# displayBoard.net
KiCad netlist of a schematic drawn in EAGLE
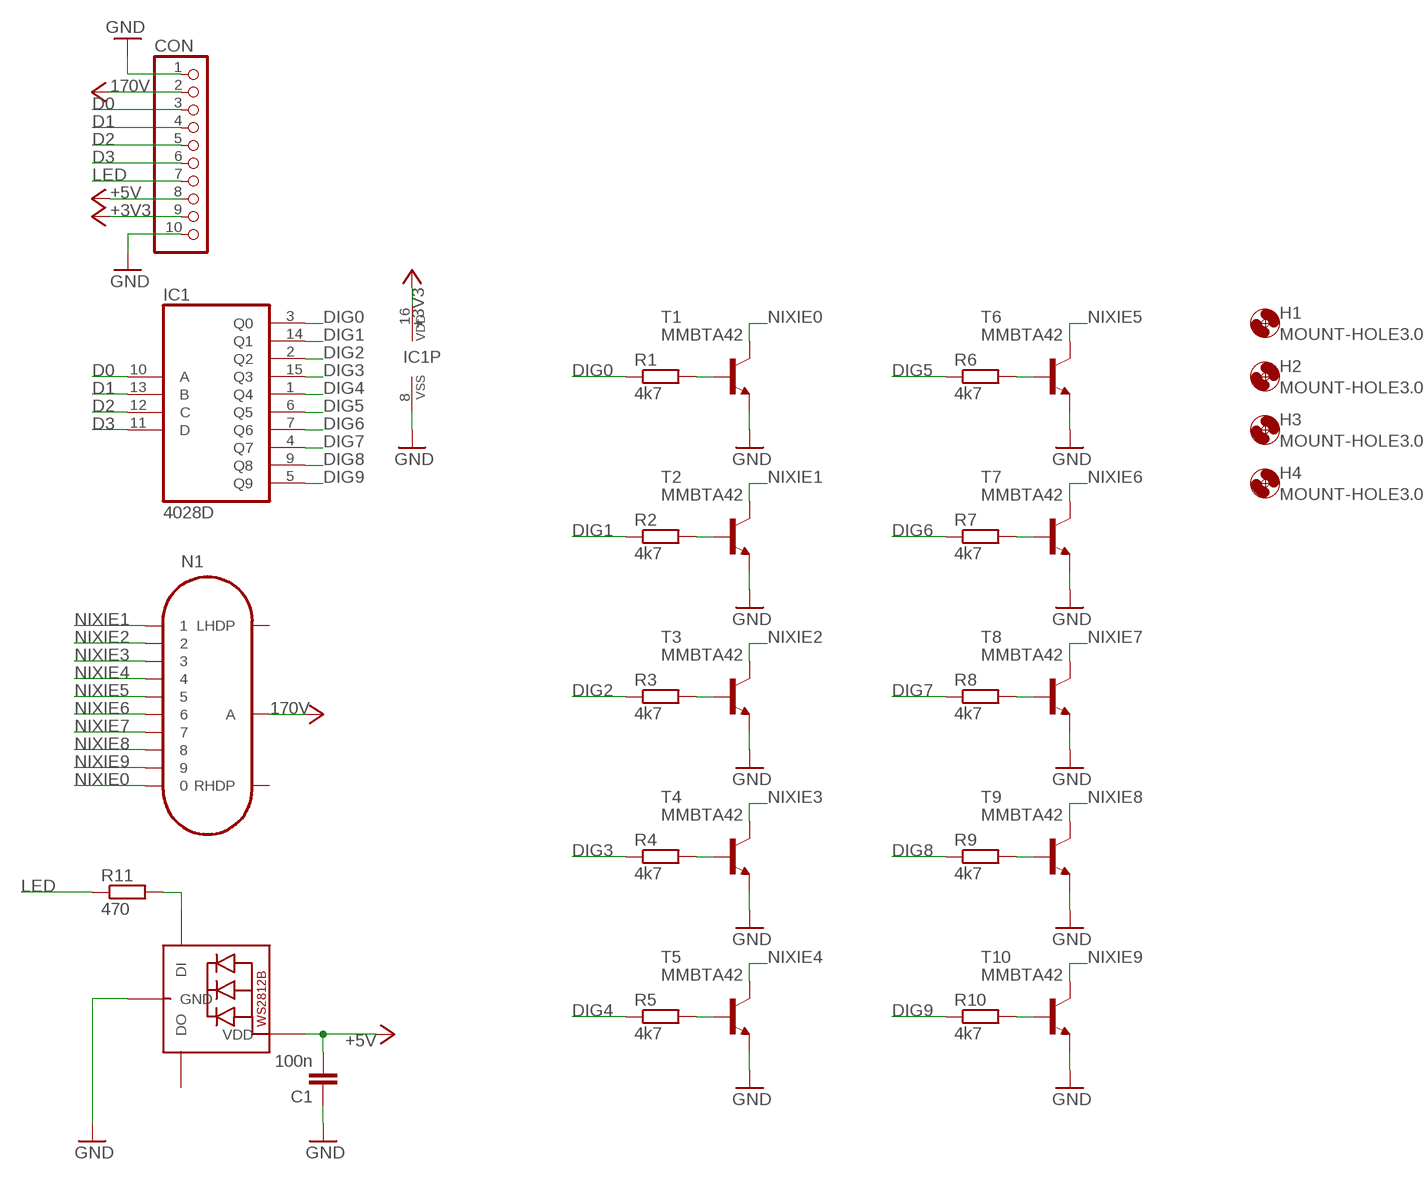
[diagram p0: schematic, sheet 1]

(export (version "E")
  (design (tool "Eeschema 10.0.6"))
  (components
    (comp (ref "C1")
      (value "100n")
      (footprint "eagle-import:C0603")
      (libsource (lib "eagle-import") (part "C-EUC0603"))
    )
    (comp (ref "CON")
      (value "PINHD-1X10")
      (footprint "eagle-import:1X10")
      (libsource (lib "eagle-import") (part "PINHD-1X10"))
    )
    (comp (ref "H1")
      (value "MOUNT-HOLE3.0")
      (footprint "eagle-import:3,0")
      (libsource (lib "eagle-import") (part "MOUNT-HOLE3.0"))
    )
    (comp (ref "H2")
      (value "MOUNT-HOLE3.0")
      (footprint "eagle-import:3,0")
      (libsource (lib "eagle-import") (part "MOUNT-HOLE3.0"))
    )
    (comp (ref "H3")
      (value "MOUNT-HOLE3.0")
      (footprint "eagle-import:3,0")
      (libsource (lib "eagle-import") (part "MOUNT-HOLE3.0"))
    )
    (comp (ref "H4")
      (value "MOUNT-HOLE3.0")
      (footprint "eagle-import:3,0")
      (libsource (lib "eagle-import") (part "MOUNT-HOLE3.0"))
    )
    (comp (ref "IC1")
      (value "4028D")
      (footprint "eagle-import:SO16")
      (libsource (lib "eagle-import") (part "4028D"))
    )
    (comp (ref "LED1")
      (value "WS2812B_5050N")
      (footprint "eagle-import:WS2812B-NARROW")
      (libsource (lib "eagle-import") (part "WS2812B_5050N"))
    )
    (comp (ref "N1")
      (value "IN-14")
      (footprint "eagle-import:IN-14")
      (libsource (lib "eagle-import") (part "IN-14"))
    )
    (comp (ref "R1")
      (value "4k7")
      (footprint "eagle-import:R0603")
      (libsource (lib "eagle-import") (part "R-EU_R0603"))
    )
    (comp (ref "R2")
      (value "4k7")
      (footprint "eagle-import:R0603")
      (libsource (lib "eagle-import") (part "R-EU_R0603"))
    )
    (comp (ref "R3")
      (value "4k7")
      (footprint "eagle-import:R0603")
      (libsource (lib "eagle-import") (part "R-EU_R0603"))
    )
    (comp (ref "R4")
      (value "4k7")
      (footprint "eagle-import:R0603")
      (libsource (lib "eagle-import") (part "R-EU_R0603"))
    )
    (comp (ref "R5")
      (value "4k7")
      (footprint "eagle-import:R0603")
      (libsource (lib "eagle-import") (part "R-EU_R0603"))
    )
    (comp (ref "R6")
      (value "4k7")
      (footprint "eagle-import:R0603")
      (libsource (lib "eagle-import") (part "R-EU_R0603"))
    )
    (comp (ref "R7")
      (value "4k7")
      (footprint "eagle-import:R0603")
      (libsource (lib "eagle-import") (part "R-EU_R0603"))
    )
    (comp (ref "R8")
      (value "4k7")
      (footprint "eagle-import:R0603")
      (libsource (lib "eagle-import") (part "R-EU_R0603"))
    )
    (comp (ref "R9")
      (value "4k7")
      (footprint "eagle-import:R0603")
      (libsource (lib "eagle-import") (part "R-EU_R0603"))
    )
    (comp (ref "R10")
      (value "4k7")
      (footprint "eagle-import:R0603")
      (libsource (lib "eagle-import") (part "R-EU_R0603"))
    )
    (comp (ref "R11")
      (value "470")
      (footprint "eagle-import:R0603")
      (libsource (lib "eagle-import") (part "R-EU_R0603"))
    )
    (comp (ref "T1")
      (value "MMBTA42")
      (footprint "eagle-import:SOT23-BEC")
      (libsource (lib "eagle-import") (part "-NPN-SOT23-BECMMBTA42LT1"))
    )
    (comp (ref "T2")
      (value "MMBTA42")
      (footprint "eagle-import:SOT23-BEC")
      (libsource (lib "eagle-import") (part "-NPN-SOT23-BECMMBTA42LT1"))
    )
    (comp (ref "T3")
      (value "MMBTA42")
      (footprint "eagle-import:SOT23-BEC")
      (libsource (lib "eagle-import") (part "-NPN-SOT23-BECMMBTA42LT1"))
    )
    (comp (ref "T4")
      (value "MMBTA42")
      (footprint "eagle-import:SOT23-BEC")
      (libsource (lib "eagle-import") (part "-NPN-SOT23-BECMMBTA42LT1"))
    )
    (comp (ref "T5")
      (value "MMBTA42")
      (footprint "eagle-import:SOT23-BEC")
      (libsource (lib "eagle-import") (part "-NPN-SOT23-BECMMBTA42LT1"))
    )
    (comp (ref "T6")
      (value "MMBTA42")
      (footprint "eagle-import:SOT23-BEC")
      (libsource (lib "eagle-import") (part "-NPN-SOT23-BECMMBTA42LT1"))
    )
    (comp (ref "T7")
      (value "MMBTA42")
      (footprint "eagle-import:SOT23-BEC")
      (libsource (lib "eagle-import") (part "-NPN-SOT23-BECMMBTA42LT1"))
    )
    (comp (ref "T8")
      (value "MMBTA42")
      (footprint "eagle-import:SOT23-BEC")
      (libsource (lib "eagle-import") (part "-NPN-SOT23-BECMMBTA42LT1"))
    )
    (comp (ref "T9")
      (value "MMBTA42")
      (footprint "eagle-import:SOT23-BEC")
      (libsource (lib "eagle-import") (part "-NPN-SOT23-BECMMBTA42LT1"))
    )
    (comp (ref "T10")
      (value "MMBTA42")
      (footprint "eagle-import:SOT23-BEC")
      (libsource (lib "eagle-import") (part "-NPN-SOT23-BECMMBTA42LT1"))
    )
  )
  (nets
    (net (code "1") (name "+3V3") (class "Default")
      (node (ref "CON") (pin "9") (pinfunction "9_9") (pintype "passive"))
      (node (ref "IC1") (pin "16") (pinfunction "VDD_16") (pintype "power_in"))
    )
    (net (code "2") (name "+5V") (class "Default")
      (node (ref "C1") (pin "2") (pinfunction "2_2") (pintype "passive"))
      (node (ref "CON") (pin "8") (pinfunction "8_8") (pintype "passive"))
      (node (ref "LED1") (pin "1-VDD") (pinfunction "VDD_1-VDD") (pintype "power_in"))
    )
    (net (code "3") (name "/D0") (class "Default")
      (node (ref "CON") (pin "3") (pinfunction "3_3") (pintype "passive"))
      (node (ref "IC1") (pin "10") (pinfunction "A_10") (pintype "input"))
    )
    (net (code "4") (name "/D1") (class "Default")
      (node (ref "CON") (pin "4") (pinfunction "4_4") (pintype "passive"))
      (node (ref "IC1") (pin "13") (pinfunction "B_13") (pintype "input"))
    )
    (net (code "5") (name "/D2") (class "Default")
      (node (ref "CON") (pin "5") (pinfunction "5_5") (pintype "passive"))
      (node (ref "IC1") (pin "12") (pinfunction "C_12") (pintype "input"))
    )
    (net (code "6") (name "/D3") (class "Default")
      (node (ref "CON") (pin "6") (pinfunction "6_6") (pintype "passive"))
      (node (ref "IC1") (pin "11") (pinfunction "D_11") (pintype "input"))
    )
    (net (code "7") (name "/DIG0") (class "Default")
      (node (ref "IC1") (pin "3") (pinfunction "Q0_3") (pintype "output"))
      (node (ref "R1") (pin "1") (pinfunction "1_1") (pintype "passive"))
    )
    (net (code "8") (name "/DIG1") (class "Default")
      (node (ref "IC1") (pin "14") (pinfunction "Q1_14") (pintype "output"))
      (node (ref "R2") (pin "1") (pinfunction "1_1") (pintype "passive"))
    )
    (net (code "9") (name "/DIG2") (class "Default")
      (node (ref "IC1") (pin "2") (pinfunction "Q2_2") (pintype "output"))
      (node (ref "R3") (pin "1") (pinfunction "1_1") (pintype "passive"))
    )
    (net (code "10") (name "/DIG3") (class "Default")
      (node (ref "IC1") (pin "15") (pinfunction "Q3_15") (pintype "output"))
      (node (ref "R4") (pin "1") (pinfunction "1_1") (pintype "passive"))
    )
    (net (code "11") (name "/DIG4") (class "Default")
      (node (ref "IC1") (pin "1") (pinfunction "Q4_1") (pintype "output"))
      (node (ref "R5") (pin "1") (pinfunction "1_1") (pintype "passive"))
    )
    (net (code "12") (name "/DIG5") (class "Default")
      (node (ref "IC1") (pin "6") (pinfunction "Q5_6") (pintype "output"))
      (node (ref "R6") (pin "1") (pinfunction "1_1") (pintype "passive"))
    )
    (net (code "13") (name "/DIG6") (class "Default")
      (node (ref "IC1") (pin "7") (pinfunction "Q6_7") (pintype "output"))
      (node (ref "R7") (pin "1") (pinfunction "1_1") (pintype "passive"))
    )
    (net (code "14") (name "/DIG7") (class "Default")
      (node (ref "IC1") (pin "4") (pinfunction "Q7_4") (pintype "output"))
      (node (ref "R8") (pin "1") (pinfunction "1_1") (pintype "passive"))
    )
    (net (code "15") (name "/DIG8") (class "Default")
      (node (ref "IC1") (pin "9") (pinfunction "Q8_9") (pintype "output"))
      (node (ref "R9") (pin "1") (pinfunction "1_1") (pintype "passive"))
    )
    (net (code "16") (name "/DIG9") (class "Default")
      (node (ref "IC1") (pin "5") (pinfunction "Q9_5") (pintype "output"))
      (node (ref "R10") (pin "1") (pinfunction "1_1") (pintype "passive"))
    )
    (net (code "17") (name "/LED") (class "Default")
      (node (ref "CON") (pin "7") (pinfunction "7_7") (pintype "passive"))
      (node (ref "R11") (pin "1") (pinfunction "1_1") (pintype "passive"))
    )
    (net (code "18") (name "/NIXIE0") (class "Default")
      (node (ref "N1") (pin "0") (pinfunction "0_0") (pintype "bidirectional"))
      (node (ref "T1") (pin "C") (pinfunction "C_C") (pintype "passive"))
    )
    (net (code "19") (name "/NIXIE1") (class "Default")
      (node (ref "N1") (pin "1") (pinfunction "1_1") (pintype "bidirectional"))
      (node (ref "T2") (pin "C") (pinfunction "C_C") (pintype "passive"))
    )
    (net (code "20") (name "/NIXIE2") (class "Default")
      (node (ref "N1") (pin "2") (pinfunction "2_2") (pintype "bidirectional"))
      (node (ref "T3") (pin "C") (pinfunction "C_C") (pintype "passive"))
    )
    (net (code "21") (name "/NIXIE3") (class "Default")
      (node (ref "N1") (pin "3") (pinfunction "3_3") (pintype "bidirectional"))
      (node (ref "T4") (pin "C") (pinfunction "C_C") (pintype "passive"))
    )
    (net (code "22") (name "/NIXIE4") (class "Default")
      (node (ref "N1") (pin "4") (pinfunction "4_4") (pintype "bidirectional"))
      (node (ref "T5") (pin "C") (pinfunction "C_C") (pintype "passive"))
    )
    (net (code "23") (name "/NIXIE5") (class "Default")
      (node (ref "N1") (pin "5") (pinfunction "5_5") (pintype "bidirectional"))
      (node (ref "T6") (pin "C") (pinfunction "C_C") (pintype "passive"))
    )
    (net (code "24") (name "/NIXIE6") (class "Default")
      (node (ref "N1") (pin "6") (pinfunction "6_6") (pintype "bidirectional"))
      (node (ref "T7") (pin "C") (pinfunction "C_C") (pintype "passive"))
    )
    (net (code "25") (name "/NIXIE7") (class "Default")
      (node (ref "N1") (pin "7") (pinfunction "7_7") (pintype "bidirectional"))
      (node (ref "T8") (pin "C") (pinfunction "C_C") (pintype "passive"))
    )
    (net (code "26") (name "/NIXIE8") (class "Default")
      (node (ref "N1") (pin "8") (pinfunction "8_8") (pintype "bidirectional"))
      (node (ref "T9") (pin "C") (pinfunction "C_C") (pintype "passive"))
    )
    (net (code "27") (name "/NIXIE9") (class "Default")
      (node (ref "N1") (pin "9") (pinfunction "9_9") (pintype "bidirectional"))
      (node (ref "T10") (pin "C") (pinfunction "C_C") (pintype "passive"))
    )
    (net (code "28") (name "170V") (class "Default")
      (node (ref "CON") (pin "2") (pinfunction "2_2") (pintype "passive"))
      (node (ref "N1") (pin "A") (pinfunction "A_A") (pintype "bidirectional"))
    )
    (net (code "29") (name "GND") (class "Default")
      (node (ref "C1") (pin "1") (pinfunction "1_1") (pintype "passive"))
      (node (ref "CON") (pin "1") (pinfunction "1_1") (pintype "passive"))
      (node (ref "CON") (pin "10") (pinfunction "10_10") (pintype "passive"))
      (node (ref "IC1") (pin "8") (pinfunction "VSS_8") (pintype "power_in"))
      (node (ref "LED1") (pin "3-GND") (pinfunction "GND_3-GND") (pintype "power_in"))
      (node (ref "T1") (pin "E") (pinfunction "E_E") (pintype "passive"))
      (node (ref "T10") (pin "E") (pinfunction "E_E") (pintype "passive"))
      (node (ref "T2") (pin "E") (pinfunction "E_E") (pintype "passive"))
      (node (ref "T3") (pin "E") (pinfunction "E_E") (pintype "passive"))
      (node (ref "T4") (pin "E") (pinfunction "E_E") (pintype "passive"))
      (node (ref "T5") (pin "E") (pinfunction "E_E") (pintype "passive"))
      (node (ref "T6") (pin "E") (pinfunction "E_E") (pintype "passive"))
      (node (ref "T7") (pin "E") (pinfunction "E_E") (pintype "passive"))
      (node (ref "T8") (pin "E") (pinfunction "E_E") (pintype "passive"))
      (node (ref "T9") (pin "E") (pinfunction "E_E") (pintype "passive"))
    )
    (net (code "30") (name "Net-(LED1-DI)") (class "Default")
      (node (ref "LED1") (pin "4-DIN") (pinfunction "DI_4-DIN") (pintype "input"))
      (node (ref "R11") (pin "2") (pinfunction "2_2") (pintype "passive"))
    )
    (net (code "31") (name "Net-(R1-Pad2)") (class "Default")
      (node (ref "R1") (pin "2") (pinfunction "2_2") (pintype "passive"))
      (node (ref "T1") (pin "B") (pinfunction "B_B") (pintype "passive"))
    )
    (net (code "32") (name "Net-(R2-Pad2)") (class "Default")
      (node (ref "R2") (pin "2") (pinfunction "2_2") (pintype "passive"))
      (node (ref "T2") (pin "B") (pinfunction "B_B") (pintype "passive"))
    )
    (net (code "33") (name "Net-(R3-Pad2)") (class "Default")
      (node (ref "R3") (pin "2") (pinfunction "2_2") (pintype "passive"))
      (node (ref "T3") (pin "B") (pinfunction "B_B") (pintype "passive"))
    )
    (net (code "34") (name "Net-(R4-Pad2)") (class "Default")
      (node (ref "R4") (pin "2") (pinfunction "2_2") (pintype "passive"))
      (node (ref "T4") (pin "B") (pinfunction "B_B") (pintype "passive"))
    )
    (net (code "35") (name "Net-(R5-Pad2)") (class "Default")
      (node (ref "R5") (pin "2") (pinfunction "2_2") (pintype "passive"))
      (node (ref "T5") (pin "B") (pinfunction "B_B") (pintype "passive"))
    )
    (net (code "36") (name "Net-(R6-Pad2)") (class "Default")
      (node (ref "R6") (pin "2") (pinfunction "2_2") (pintype "passive"))
      (node (ref "T6") (pin "B") (pinfunction "B_B") (pintype "passive"))
    )
    (net (code "37") (name "Net-(R7-Pad2)") (class "Default")
      (node (ref "R7") (pin "2") (pinfunction "2_2") (pintype "passive"))
      (node (ref "T7") (pin "B") (pinfunction "B_B") (pintype "passive"))
    )
    (net (code "38") (name "Net-(R8-Pad2)") (class "Default")
      (node (ref "R8") (pin "2") (pinfunction "2_2") (pintype "passive"))
      (node (ref "T8") (pin "B") (pinfunction "B_B") (pintype "passive"))
    )
    (net (code "39") (name "Net-(R9-Pad2)") (class "Default")
      (node (ref "R9") (pin "2") (pinfunction "2_2") (pintype "passive"))
      (node (ref "T9") (pin "B") (pinfunction "B_B") (pintype "passive"))
    )
    (net (code "40") (name "Net-(R10-Pad2)") (class "Default")
      (node (ref "R10") (pin "2") (pinfunction "2_2") (pintype "passive"))
      (node (ref "T10") (pin "B") (pinfunction "B_B") (pintype "passive"))
    )
    (net (code "41") (name "unconnected-(LED1-DO-Pad2-DOUT)") (class "Default")
      (node (ref "LED1") (pin "2-DOUT") (pinfunction "DO_2-DOUT") (pintype "output"))
    )
    (net (code "42") (name "unconnected-(N1-PadLHDP)") (class "Default")
      (node (ref "N1") (pin "LHDP") (pinfunction "LHDP_LHDP") (pintype "bidirectional"))
    )
    (net (code "43") (name "unconnected-(N1-PadRHDP)") (class "Default")
      (node (ref "N1") (pin "RHDP") (pinfunction "RHDP_RHDP") (pintype "bidirectional"))
    )
  )
)
